# imu__EDA.net
KiCad netlist of a schematic drawn in EasyEDA
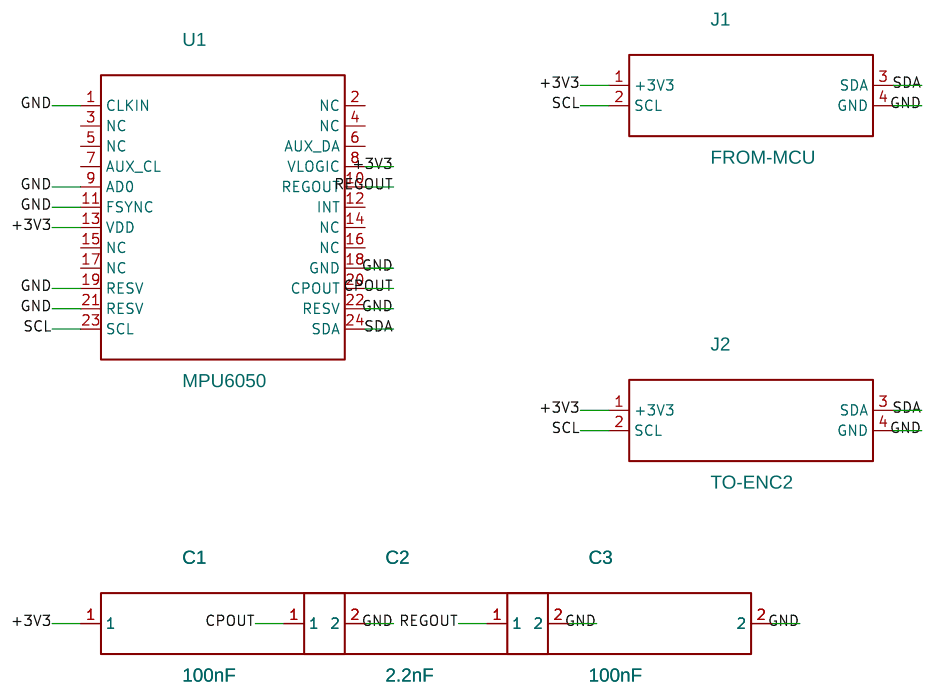
[diagram p0: schematic sheet]

(export (version "E")
  (design (tool "Eeschema 10.0.6"))
  (components
    (comp (ref "C1") (value "100nF") (libsource (lib "") (part "Unknown_300_500")))
    (comp (ref "C2") (value "2.2nF") (libsource (lib "") (part "Unknown_400_500")))
    (comp (ref "C3") (value "100nF") (libsource (lib "") (part "Unknown_500_500")))
    (comp (ref "J1") (value "FROM-MCU") (libsource (lib "") (part "Unknown_560_240")))
    (comp (ref "J2") (value "TO-ENC2") (libsource (lib "") (part "Unknown_560_400")))
    (comp (ref "U1") (value "MPU6050") (libsource (lib "") (part "Unknown_300_300")))
  )
  (nets
    (net (code "1") (name "/+3V3") (class "Default")
      (node (ref "C1") (pin "1") (pinfunction "1_1") (pintype "unspecified"))
      (node (ref "J1") (pin "1") (pinfunction "+3V3_1") (pintype "unspecified"))
      (node (ref "J2") (pin "1") (pinfunction "+3V3_1") (pintype "unspecified"))
      (node (ref "U1") (pin "13") (pinfunction "VDD_13") (pintype "unspecified"))
      (node (ref "U1") (pin "8") (pinfunction "VLOGIC_8") (pintype "unspecified"))
    )
    (net (code "2") (name "/CPOUT") (class "Default")
      (node (ref "C2") (pin "1") (pinfunction "1_1") (pintype "unspecified"))
      (node (ref "U1") (pin "20") (pinfunction "CPOUT_20") (pintype "unspecified"))
    )
    (net (code "3") (name "/GND") (class "Default")
      (node (ref "C1") (pin "2") (pinfunction "2_2") (pintype "unspecified"))
      (node (ref "C2") (pin "2") (pinfunction "2_2") (pintype "unspecified"))
      (node (ref "C3") (pin "2") (pinfunction "2_2") (pintype "unspecified"))
      (node (ref "J1") (pin "4") (pinfunction "GND_4") (pintype "unspecified"))
      (node (ref "J2") (pin "4") (pinfunction "GND_4") (pintype "unspecified"))
      (node (ref "U1") (pin "1") (pinfunction "CLKIN_1") (pintype "unspecified"))
      (node (ref "U1") (pin "11") (pinfunction "FSYNC_11") (pintype "unspecified"))
      (node (ref "U1") (pin "18") (pinfunction "GND_18") (pintype "unspecified"))
      (node (ref "U1") (pin "19") (pinfunction "RESV_19") (pintype "unspecified"))
      (node (ref "U1") (pin "21") (pinfunction "RESV_21") (pintype "unspecified"))
      (node (ref "U1") (pin "22") (pinfunction "RESV_22") (pintype "unspecified"))
      (node (ref "U1") (pin "9") (pinfunction "AD0_9") (pintype "unspecified"))
    )
    (net (code "4") (name "/REGOUT") (class "Default")
      (node (ref "C3") (pin "1") (pinfunction "1_1") (pintype "unspecified"))
      (node (ref "U1") (pin "10") (pinfunction "REGOUT_10") (pintype "unspecified"))
    )
    (net (code "5") (name "/SCL") (class "Default")
      (node (ref "J1") (pin "2") (pinfunction "SCL_2") (pintype "unspecified"))
      (node (ref "J2") (pin "2") (pinfunction "SCL_2") (pintype "unspecified"))
      (node (ref "U1") (pin "23") (pinfunction "SCL_23") (pintype "unspecified"))
    )
    (net (code "6") (name "/SDA") (class "Default")
      (node (ref "J1") (pin "3") (pinfunction "SDA_3") (pintype "unspecified"))
      (node (ref "J2") (pin "3") (pinfunction "SDA_3") (pintype "unspecified"))
      (node (ref "U1") (pin "24") (pinfunction "SDA_24") (pintype "unspecified"))
    )
    (net (code "7") (name "unconnected-(U1-AUX_CL-Pad7)") (class "Default")
      (node (ref "U1") (pin "7") (pinfunction "AUX_CL_7") (pintype "unspecified"))
    )
    (net (code "8") (name "unconnected-(U1-AUX_DA-Pad6)") (class "Default")
      (node (ref "U1") (pin "6") (pinfunction "AUX_DA_6") (pintype "unspecified"))
    )
    (net (code "9") (name "unconnected-(U1-INT-Pad12)") (class "Default")
      (node (ref "U1") (pin "12") (pinfunction "INT_12") (pintype "unspecified"))
    )
    (net (code "10") (name "unconnected-(U1-NC-Pad2)") (class "Default")
      (node (ref "U1") (pin "2") (pinfunction "NC_2") (pintype "unspecified"))
    )
    (net (code "11") (name "unconnected-(U1-NC-Pad3)") (class "Default")
      (node (ref "U1") (pin "3") (pinfunction "NC_3") (pintype "unspecified"))
    )
    (net (code "12") (name "unconnected-(U1-NC-Pad4)") (class "Default")
      (node (ref "U1") (pin "4") (pinfunction "NC_4") (pintype "unspecified"))
    )
    (net (code "13") (name "unconnected-(U1-NC-Pad5)") (class "Default")
      (node (ref "U1") (pin "5") (pinfunction "NC_5") (pintype "unspecified"))
    )
    (net (code "14") (name "unconnected-(U1-NC-Pad14)") (class "Default")
      (node (ref "U1") (pin "14") (pinfunction "NC_14") (pintype "unspecified"))
    )
    (net (code "15") (name "unconnected-(U1-NC-Pad15)") (class "Default")
      (node (ref "U1") (pin "15") (pinfunction "NC_15") (pintype "unspecified"))
    )
    (net (code "16") (name "unconnected-(U1-NC-Pad16)") (class "Default")
      (node (ref "U1") (pin "16") (pinfunction "NC_16") (pintype "unspecified"))
    )
    (net (code "17") (name "unconnected-(U1-NC-Pad17)") (class "Default")
      (node (ref "U1") (pin "17") (pinfunction "NC_17") (pintype "unspecified"))
    )
  )
)
